# INPUT_SECTION.net
KiCad netlist of a schematic drawn in Altium Designer
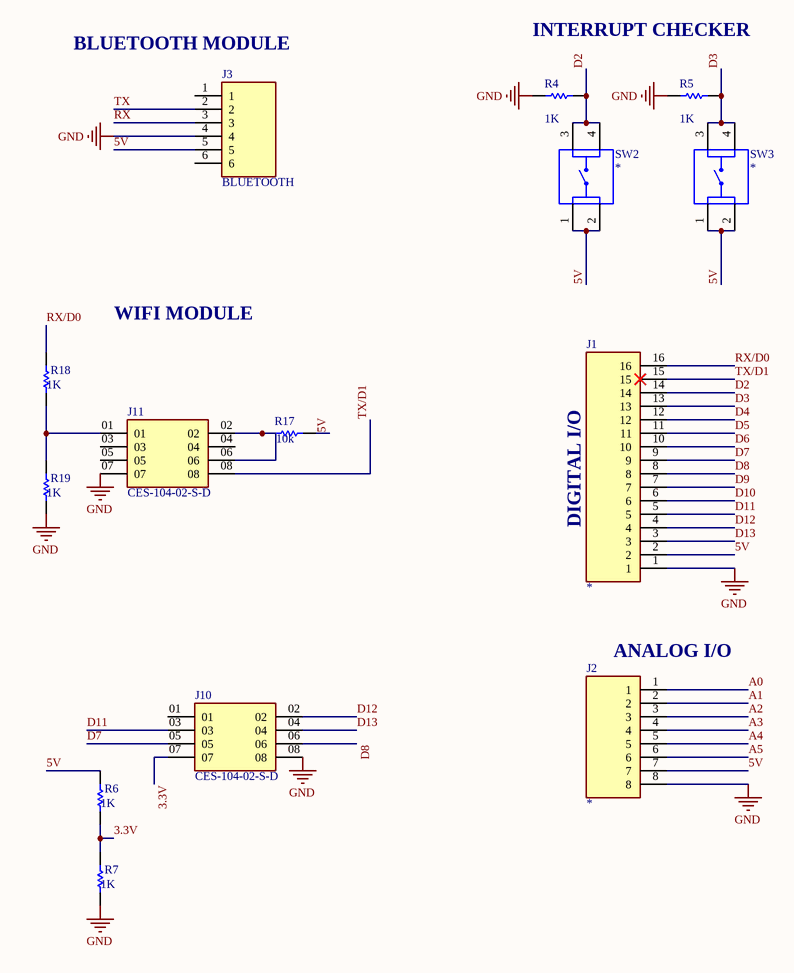
[diagram p0: INPUT SECTION.SchDoc]

(export (version "E")
  (design (tool "Eeschema 10.0.6"))
  (components
    (comp (ref "J1")
      (value "1-215297-6")
      (footprint "TE_1-215297-6")
      (fields (field (name "MF") "TE Connectivity") (field (name "COMMENT_1") "*"))
      (libsource (lib "16pin female header 3D") (part "1-215297-6"))
    )
    (comp (ref "J2")
      (value "5-534237-6")
      (footprint "TE_5-534237-6")
      (description "Connector Socket Strip Receptacle 8 Position 2.54mm Solder Straight Through Hole")
      (fields (field (name "MF") "TE Connectivity") (field (name "COMMENT_1") "*"))
      (libsource (lib "8pin female header 3D") (part "5-534237-6"))
    )
    (comp (ref "J3")
      (value "BLUETOOTH")
      (footprint "HDRV6W70P0X254_1X6_1564X250X865P")
      (description "Connector")
      (fields
        (field (name "MANUFACTURER_PART_NUMBER") "M20-7820646")
        (field (name "MOUSER PART NUMBER") "855-M20-7820646")
      )
      (libsource (lib "6pin female header 3D") (part "M20-7820646"))
    )
    (comp (ref "J10")
      (value "CES-104-02-S-D")
      (footprint "SAMTEC_CES-104-02-S-D")
      (description "8 Position Receptacle Connector Through Hole")
      (fields (field (name "MF") "Samtec"))
      (libsource (lib "8 position female header") (part "CES-104-02-S-D"))
    )
    (comp (ref "J11")
      (value "CES-104-02-S-D")
      (footprint "SAMTEC_CES-104-02-S-D")
      (description "8 Position Receptacle Connector Through Hole")
      (fields (field (name "MF") "Samtec"))
      (libsource (lib "8 position female header") (part "CES-104-02-S-D"))
    )
    (comp (ref "R4")
      (value "1K")
      (footprint "AXIAL-0.5")
      (description "Semiconductor Resistor")
      (fields (field (name "PUBLISHER") "Altium Limited"))
      (libsource (lib "Miscellaneous Devices") (part "Res Semi"))
    )
    (comp (ref "R5")
      (value "1K")
      (footprint "AXIAL-0.5")
      (description "Semiconductor Resistor")
      (fields (field (name "PUBLISHER") "Altium Limited"))
      (libsource (lib "Miscellaneous Devices") (part "Res Semi"))
    )
    (comp (ref "R6")
      (value "1K")
      (footprint "AXIAL-0.5")
      (description "Semiconductor Resistor")
      (fields (field (name "PUBLISHER") "Altium Limited"))
      (libsource (lib "Miscellaneous Devices") (part "Res Semi"))
    )
    (comp (ref "R7")
      (value "1K")
      (footprint "AXIAL-0.5")
      (description "Semiconductor Resistor")
      (fields (field (name "PUBLISHER") "Altium Limited"))
      (libsource (lib "Miscellaneous Devices") (part "Res Semi"))
    )
    (comp (ref "R17")
      (value "10k")
      (footprint "AXIAL-0.5")
      (description "Semiconductor Resistor")
      (fields (field (name "PUBLISHER") "Altium Limited"))
      (libsource (lib "Miscellaneous Devices") (part "Res Semi"))
    )
    (comp (ref "R18")
      (value "1K")
      (footprint "AXIAL-0.5")
      (description "Semiconductor Resistor")
      (fields (field (name "PUBLISHER") "Altium Limited"))
      (libsource (lib "Miscellaneous Devices") (part "Res Semi"))
    )
    (comp (ref "R19")
      (value "1K")
      (footprint "AXIAL-0.5")
      (description "Semiconductor Resistor")
      (fields (field (name "PUBLISHER") "Altium Limited"))
      (libsource (lib "Miscellaneous Devices") (part "Res Semi"))
    )
    (comp (ref "SW2")
      (value "1825910-6")
      (footprint "SW_1825910-6-4")
      (description "Switch Push Button OFF _ON_ SPST Round Button 0.05A 24VDC Momentary Contact PC Pins Thru-Hole")
      (fields
        (field (name "MF") "TE Connectivity")
        (field (name "DIGI-KEY_PART_NUMBER") "450-1650-ND")
        (field (name "COMMENT_1") "*")
      )
      (libsource (lib "pushbutton") (part "1825910-6"))
    )
    (comp (ref "SW3")
      (value "1825910-6")
      (footprint "SW_1825910-6-4")
      (description "Switch Push Button OFF _ON_ SPST Round Button 0.05A 24VDC Momentary Contact PC Pins Thru-Hole")
      (fields
        (field (name "MF") "TE Connectivity")
        (field (name "DIGI-KEY_PART_NUMBER") "450-1650-ND")
        (field (name "COMMENT_1") "*")
      )
      (libsource (lib "pushbutton") (part "1825910-6"))
    )
  )
  (nets
    (net (code "1") (name "/3.3V") (class "Default")
      (node (ref "J10") (pin "07") (pinfunction "07_07") (pintype "passive"))
      (node (ref "R6") (pin "1") (pinfunction "1_1") (pintype "passive"))
      (node (ref "R7") (pin "2") (pinfunction "2_2") (pintype "passive"))
    )
    (net (code "2") (name "/5V") (class "Default")
      (node (ref "J1") (pin "2") (pinfunction "2_2") (pintype "passive"))
      (node (ref "J2") (pin "7") (pinfunction "7_7") (pintype "passive"))
      (node (ref "J3") (pin "5") (pinfunction "5_5") (pintype "passive"))
      (node (ref "R17") (pin "1") (pinfunction "1_1") (pintype "passive"))
      (node (ref "R6") (pin "2") (pinfunction "2_2") (pintype "passive"))
      (node (ref "SW2") (pin "1") (pinfunction "1_1") (pintype "passive"))
      (node (ref "SW2") (pin "2") (pinfunction "2_2") (pintype "passive"))
      (node (ref "SW3") (pin "1") (pinfunction "1_1") (pintype "passive"))
      (node (ref "SW3") (pin "2") (pinfunction "2_2") (pintype "passive"))
    )
    (net (code "3") (name "/A0") (class "Default")
      (node (ref "J2") (pin "1") (pinfunction "1_1") (pintype "passive"))
    )
    (net (code "4") (name "/A1") (class "Default")
      (node (ref "J2") (pin "2") (pinfunction "2_2") (pintype "passive"))
    )
    (net (code "5") (name "/A2") (class "Default")
      (node (ref "J2") (pin "3") (pinfunction "3_3") (pintype "passive"))
    )
    (net (code "6") (name "/A3") (class "Default")
      (node (ref "J2") (pin "4") (pinfunction "4_4") (pintype "passive"))
    )
    (net (code "7") (name "/A4") (class "Default")
      (node (ref "J2") (pin "5") (pinfunction "5_5") (pintype "passive"))
    )
    (net (code "8") (name "/A5") (class "Default")
      (node (ref "J2") (pin "6") (pinfunction "6_6") (pintype "passive"))
    )
    (net (code "9") (name "/D2") (class "Default")
      (node (ref "J1") (pin "14") (pinfunction "14_14") (pintype "passive"))
      (node (ref "R4") (pin "1") (pinfunction "1_1") (pintype "passive"))
      (node (ref "SW2") (pin "3") (pinfunction "3_3") (pintype "passive"))
      (node (ref "SW2") (pin "4") (pinfunction "4_4") (pintype "passive"))
    )
    (net (code "10") (name "/D3") (class "Default")
      (node (ref "J1") (pin "13") (pinfunction "13_13") (pintype "passive"))
      (node (ref "R5") (pin "1") (pinfunction "1_1") (pintype "passive"))
      (node (ref "SW3") (pin "3") (pinfunction "3_3") (pintype "passive"))
      (node (ref "SW3") (pin "4") (pinfunction "4_4") (pintype "passive"))
    )
    (net (code "11") (name "/D4") (class "Default")
      (node (ref "J1") (pin "12") (pinfunction "12_12") (pintype "passive"))
    )
    (net (code "12") (name "/D5") (class "Default")
      (node (ref "J1") (pin "11") (pinfunction "11_11") (pintype "passive"))
    )
    (net (code "13") (name "/D6") (class "Default")
      (node (ref "J1") (pin "10") (pinfunction "10_10") (pintype "passive"))
    )
    (net (code "14") (name "/D7") (class "Default")
      (node (ref "J1") (pin "9") (pinfunction "9_9") (pintype "passive"))
      (node (ref "J10") (pin "05") (pinfunction "05_05") (pintype "passive"))
    )
    (net (code "15") (name "/D8") (class "Default")
      (node (ref "J1") (pin "8") (pinfunction "8_8") (pintype "passive"))
      (node (ref "J10") (pin "06") (pinfunction "06_06") (pintype "passive"))
    )
    (net (code "16") (name "/D9") (class "Default")
      (node (ref "J1") (pin "7") (pinfunction "7_7") (pintype "passive"))
    )
    (net (code "17") (name "/D10") (class "Default")
      (node (ref "J1") (pin "6") (pinfunction "6_6") (pintype "passive"))
    )
    (net (code "18") (name "/D11") (class "Default")
      (node (ref "J1") (pin "5") (pinfunction "5_5") (pintype "passive"))
      (node (ref "J10") (pin "03") (pinfunction "03_03") (pintype "passive"))
    )
    (net (code "19") (name "/D12") (class "Default")
      (node (ref "J1") (pin "4") (pinfunction "4_4") (pintype "passive"))
      (node (ref "J10") (pin "02") (pinfunction "02_02") (pintype "passive"))
    )
    (net (code "20") (name "/D13") (class "Default")
      (node (ref "J1") (pin "3") (pinfunction "3_3") (pintype "passive"))
      (node (ref "J10") (pin "04") (pinfunction "04_04") (pintype "passive"))
    )
    (net (code "21") (name "/RX") (class "Default")
      (node (ref "J3") (pin "3") (pinfunction "3_3") (pintype "passive"))
    )
    (net (code "22") (name "/RX{slash}D0") (class "Default")
      (node (ref "J1") (pin "16") (pinfunction "16_16") (pintype "passive"))
      (node (ref "R18") (pin "2") (pinfunction "2_2") (pintype "passive"))
    )
    (net (code "23") (name "/TX") (class "Default")
      (node (ref "J3") (pin "2") (pinfunction "2_2") (pintype "passive"))
    )
    (net (code "24") (name "/TX{slash}D1") (class "Default")
      (node (ref "J1") (pin "15") (pinfunction "15_15") (pintype "passive"))
      (node (ref "J11") (pin "08") (pinfunction "08_08") (pintype "passive"))
    )
    (net (code "25") (name "GND") (class "Default")
      (node (ref "J1") (pin "1") (pinfunction "1_1") (pintype "passive"))
      (node (ref "J10") (pin "08") (pinfunction "08_08") (pintype "passive"))
      (node (ref "J11") (pin "07") (pinfunction "07_07") (pintype "passive"))
      (node (ref "J2") (pin "8") (pinfunction "8_8") (pintype "passive"))
      (node (ref "J3") (pin "4") (pinfunction "4_4") (pintype "passive"))
      (node (ref "R19") (pin "1") (pinfunction "1_1") (pintype "passive"))
      (node (ref "R4") (pin "2") (pinfunction "2_2") (pintype "passive"))
      (node (ref "R5") (pin "2") (pinfunction "2_2") (pintype "passive"))
      (node (ref "R7") (pin "1") (pinfunction "1_1") (pintype "passive"))
    )
    (net (code "26") (name "Net-(J11-Pad01)") (class "Default")
      (node (ref "J11") (pin "01") (pinfunction "01_01") (pintype "passive"))
      (node (ref "R18") (pin "1") (pinfunction "1_1") (pintype "passive"))
      (node (ref "R19") (pin "2") (pinfunction "2_2") (pintype "passive"))
    )
    (net (code "27") (name "Net-(J11-Pad02)") (class "Default")
      (node (ref "J11") (pin "02") (pinfunction "02_02") (pintype "passive"))
      (node (ref "J11") (pin "06") (pinfunction "06_06") (pintype "passive"))
      (node (ref "R17") (pin "2") (pinfunction "2_2") (pintype "passive"))
    )
    (net (code "28") (name "unconnected-(J3-Pad1)") (class "Default")
      (node (ref "J3") (pin "1") (pinfunction "1_1") (pintype "passive"))
    )
    (net (code "29") (name "unconnected-(J3-Pad6)") (class "Default")
      (node (ref "J3") (pin "6") (pinfunction "6_6") (pintype "passive"))
    )
    (net (code "30") (name "unconnected-(J10-Pad01)") (class "Default")
      (node (ref "J10") (pin "01") (pinfunction "01_01") (pintype "passive"))
    )
    (net (code "31") (name "unconnected-(J11-Pad03)") (class "Default")
      (node (ref "J11") (pin "03") (pinfunction "03_03") (pintype "passive"))
    )
    (net (code "32") (name "unconnected-(J11-Pad04)") (class "Default")
      (node (ref "J11") (pin "04") (pinfunction "04_04") (pintype "passive"))
    )
    (net (code "33") (name "unconnected-(J11-Pad05)") (class "Default")
      (node (ref "J11") (pin "05") (pinfunction "05_05") (pintype "passive"))
    )
  )
)
